# SCH_cam2_2024-05-21.net
KiCad netlist of a schematic drawn in EasyEDA
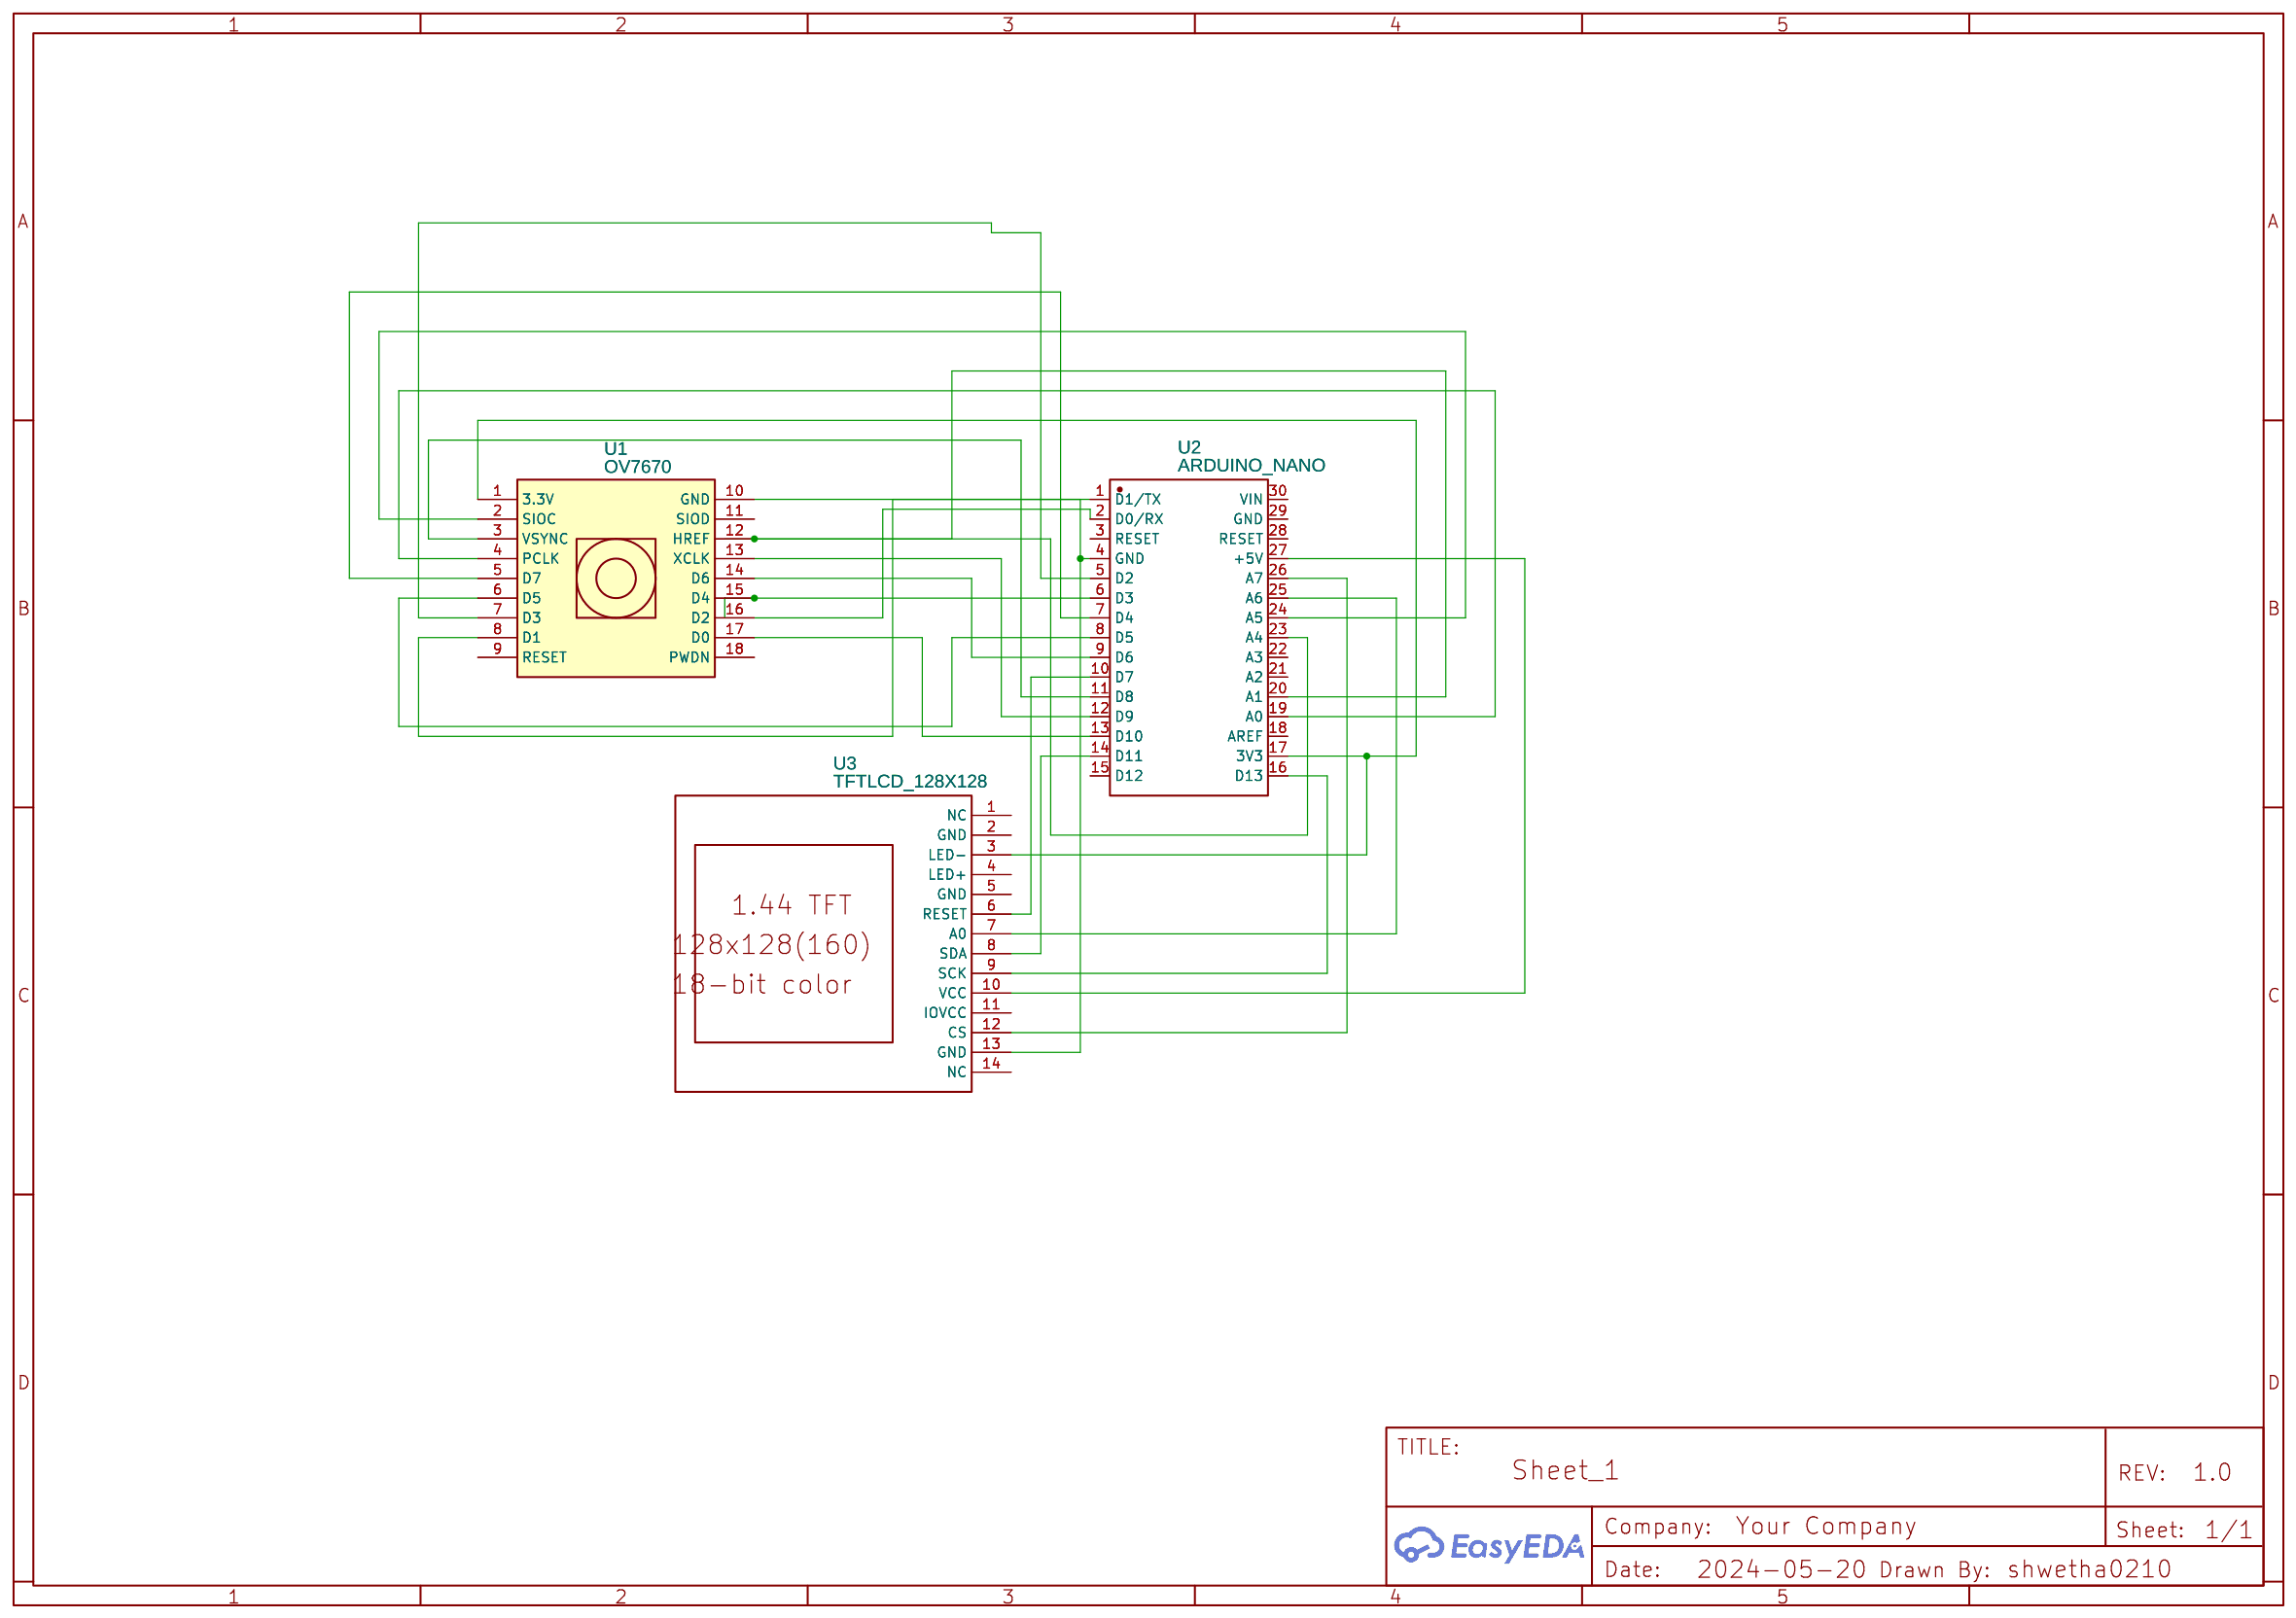
[diagram p0: schematic sheet]

(export (version "E")
  (design (tool "Eeschema 10.0.6"))
  (components
    (comp (ref "U1")
      (value "OV7670")
      (fields (field (name "Manufacturer Part") "PM254-2-09-Z-8.5"))
      (libsource (lib "") (part "OV7670"))
    )
    (comp (ref "U2") (value "ARDUINO_NANO") (libsource (lib "") (part "ARDUINO_NANO")))
    (comp (ref "U3") (value "TFTLCD_128X128") (libsource (lib "") (part "TFTLCD_128X128")))
  )
  (nets
    (net (code "1") (name "Net-(U1-3.3V)") (class "Default")
      (node (ref "U1") (pin "1") (pinfunction "3.3V_1") (pintype "unspecified"))
      (node (ref "U2") (pin "17") (pinfunction "3V3_17") (pintype "unspecified"))
      (node (ref "U3") (pin "3") (pinfunction "LED-_3") (pintype "input"))
    )
    (net (code "2") (name "Net-(U1-D0)") (class "Default")
      (node (ref "U1") (pin "17") (pinfunction "D0_17") (pintype "unspecified"))
      (node (ref "U2") (pin "13") (pinfunction "D10_13") (pintype "unspecified"))
    )
    (net (code "3") (name "Net-(U1-D1)") (class "Default")
      (node (ref "U1") (pin "8") (pinfunction "D1_8") (pintype "unspecified"))
      (node (ref "U2") (pin "1") (pinfunction "D1/TX_1") (pintype "unspecified"))
    )
    (net (code "4") (name "Net-(U1-D2)") (class "Default")
      (node (ref "U1") (pin "16") (pinfunction "D2_16") (pintype "unspecified"))
      (node (ref "U2") (pin "2") (pinfunction "D0/RX_2") (pintype "unspecified"))
    )
    (net (code "5") (name "Net-(U1-D3)") (class "Default")
      (node (ref "U1") (pin "7") (pinfunction "D3_7") (pintype "unspecified"))
      (node (ref "U2") (pin "5") (pinfunction "D2_5") (pintype "unspecified"))
    )
    (net (code "6") (name "Net-(U1-D4)") (class "Default")
      (node (ref "U1") (pin "15") (pinfunction "D4_15") (pintype "unspecified"))
      (node (ref "U2") (pin "6") (pinfunction "D3_6") (pintype "unspecified"))
    )
    (net (code "7") (name "Net-(U1-D5)") (class "Default")
      (node (ref "U1") (pin "6") (pinfunction "D5_6") (pintype "unspecified"))
      (node (ref "U2") (pin "8") (pinfunction "D5_8") (pintype "unspecified"))
    )
    (net (code "8") (name "Net-(U1-D6)") (class "Default")
      (node (ref "U1") (pin "14") (pinfunction "D6_14") (pintype "unspecified"))
      (node (ref "U2") (pin "9") (pinfunction "D6_9") (pintype "unspecified"))
    )
    (net (code "9") (name "Net-(U1-D7)") (class "Default")
      (node (ref "U1") (pin "5") (pinfunction "D7_5") (pintype "unspecified"))
      (node (ref "U2") (pin "7") (pinfunction "D4_7") (pintype "unspecified"))
    )
    (net (code "10") (name "Net-(U1-GND)") (class "Default")
      (node (ref "U1") (pin "10") (pinfunction "GND_10") (pintype "unspecified"))
      (node (ref "U2") (pin "4") (pinfunction "GND_4") (pintype "unspecified"))
      (node (ref "U3") (pin "13") (pinfunction "GND_13") (pintype "passive"))
    )
    (net (code "11") (name "Net-(U1-HREF)") (class "Default")
      (node (ref "U1") (pin "12") (pinfunction "HREF_12") (pintype "unspecified"))
      (node (ref "U2") (pin "20") (pinfunction "A1_20") (pintype "unspecified"))
      (node (ref "U2") (pin "23") (pinfunction "A4_23") (pintype "unspecified"))
    )
    (net (code "12") (name "Net-(U1-PCLK)") (class "Default")
      (node (ref "U1") (pin "4") (pinfunction "PCLK_4") (pintype "unspecified"))
      (node (ref "U2") (pin "19") (pinfunction "A0_19") (pintype "unspecified"))
    )
    (net (code "13") (name "Net-(U1-SIOC)") (class "Default")
      (node (ref "U1") (pin "2") (pinfunction "SIOC_2") (pintype "unspecified"))
      (node (ref "U2") (pin "24") (pinfunction "A5_24") (pintype "unspecified"))
    )
    (net (code "14") (name "Net-(U1-VSYNC)") (class "Default")
      (node (ref "U1") (pin "3") (pinfunction "VSYNC_3") (pintype "unspecified"))
      (node (ref "U2") (pin "11") (pinfunction "D8_11") (pintype "unspecified"))
    )
    (net (code "15") (name "Net-(U1-XCLK)") (class "Default")
      (node (ref "U1") (pin "13") (pinfunction "XCLK_13") (pintype "unspecified"))
      (node (ref "U2") (pin "12") (pinfunction "D9_12") (pintype "unspecified"))
    )
    (net (code "16") (name "Net-(U2-+5V)") (class "Default")
      (node (ref "U2") (pin "27") (pinfunction "+5V_27") (pintype "unspecified"))
      (node (ref "U3") (pin "10") (pinfunction "VCC_10") (pintype "passive"))
    )
    (net (code "17") (name "Net-(U2-A6)") (class "Default")
      (node (ref "U2") (pin "25") (pinfunction "A6_25") (pintype "unspecified"))
      (node (ref "U3") (pin "7") (pinfunction "A0_7") (pintype "input"))
    )
    (net (code "18") (name "Net-(U2-A7)") (class "Default")
      (node (ref "U2") (pin "26") (pinfunction "A7_26") (pintype "unspecified"))
      (node (ref "U3") (pin "12") (pinfunction "CS_12") (pintype "input"))
    )
    (net (code "19") (name "Net-(U2-D7)") (class "Default")
      (node (ref "U2") (pin "10") (pinfunction "D7_10") (pintype "unspecified"))
      (node (ref "U3") (pin "6") (pinfunction "RESET_6") (pintype "input"))
    )
    (net (code "20") (name "Net-(U2-D11)") (class "Default")
      (node (ref "U2") (pin "14") (pinfunction "D11_14") (pintype "unspecified"))
      (node (ref "U3") (pin "8") (pinfunction "SDA_8") (pintype "unspecified"))
    )
    (net (code "21") (name "Net-(U2-D13)") (class "Default")
      (node (ref "U2") (pin "16") (pinfunction "D13_16") (pintype "unspecified"))
      (node (ref "U3") (pin "9") (pinfunction "SCK_9") (pintype "input"))
    )
    (net (code "22") (name "unconnected-(U1-PWDN-Pad18)") (class "Default")
      (node (ref "U1") (pin "18") (pinfunction "PWDN_18") (pintype "unspecified"))
    )
    (net (code "23") (name "unconnected-(U1-RESET-Pad9)") (class "Default")
      (node (ref "U1") (pin "9") (pinfunction "RESET_9") (pintype "unspecified"))
    )
    (net (code "24") (name "unconnected-(U1-SIOD-Pad11)") (class "Default")
      (node (ref "U1") (pin "11") (pinfunction "SIOD_11") (pintype "unspecified"))
    )
    (net (code "25") (name "unconnected-(U2-A2-Pad21)") (class "Default")
      (node (ref "U2") (pin "21") (pinfunction "A2_21") (pintype "unspecified"))
    )
    (net (code "26") (name "unconnected-(U2-A3-Pad22)") (class "Default")
      (node (ref "U2") (pin "22") (pinfunction "A3_22") (pintype "unspecified"))
    )
    (net (code "27") (name "unconnected-(U2-AREF-Pad18)") (class "Default")
      (node (ref "U2") (pin "18") (pinfunction "AREF_18") (pintype "unspecified"))
    )
    (net (code "28") (name "unconnected-(U2-D12-Pad15)") (class "Default")
      (node (ref "U2") (pin "15") (pinfunction "D12_15") (pintype "unspecified"))
    )
    (net (code "29") (name "unconnected-(U2-GND-Pad29)") (class "Default")
      (node (ref "U2") (pin "29") (pinfunction "GND_29") (pintype "unspecified"))
    )
    (net (code "30") (name "unconnected-(U2-RESET-Pad3)") (class "Default")
      (node (ref "U2") (pin "3") (pinfunction "RESET_3") (pintype "unspecified"))
    )
    (net (code "31") (name "unconnected-(U2-RESET-Pad28)") (class "Default")
      (node (ref "U2") (pin "28") (pinfunction "RESET_28") (pintype "unspecified"))
    )
    (net (code "32") (name "unconnected-(U2-VIN-Pad30)") (class "Default")
      (node (ref "U2") (pin "30") (pinfunction "VIN_30") (pintype "unspecified"))
    )
    (net (code "33") (name "unconnected-(U3-GND-Pad2)") (class "Default")
      (node (ref "U3") (pin "2") (pinfunction "GND_2") (pintype "passive"))
    )
    (net (code "34") (name "unconnected-(U3-GND-Pad5)") (class "Default")
      (node (ref "U3") (pin "5") (pinfunction "GND_5") (pintype "passive"))
    )
    (net (code "35") (name "unconnected-(U3-IOVCC-Pad11)") (class "Default")
      (node (ref "U3") (pin "11") (pinfunction "IOVCC_11") (pintype "passive"))
    )
    (net (code "36") (name "unconnected-(U3-LED+-Pad4)") (class "Default")
      (node (ref "U3") (pin "4") (pinfunction "LED+_4") (pintype "input"))
    )
    (net (code "37") (name "unconnected-(U3-NC-Pad1)") (class "Default")
      (node (ref "U3") (pin "1") (pinfunction "NC_1") (pintype "passive"))
    )
    (net (code "38") (name "unconnected-(U3-NC-Pad14)") (class "Default")
      (node (ref "U3") (pin "14") (pinfunction "NC_14") (pintype "passive"))
    )
  )
)
